# Simple8085.net
KiCad netlist of a schematic drawn in EAGLE
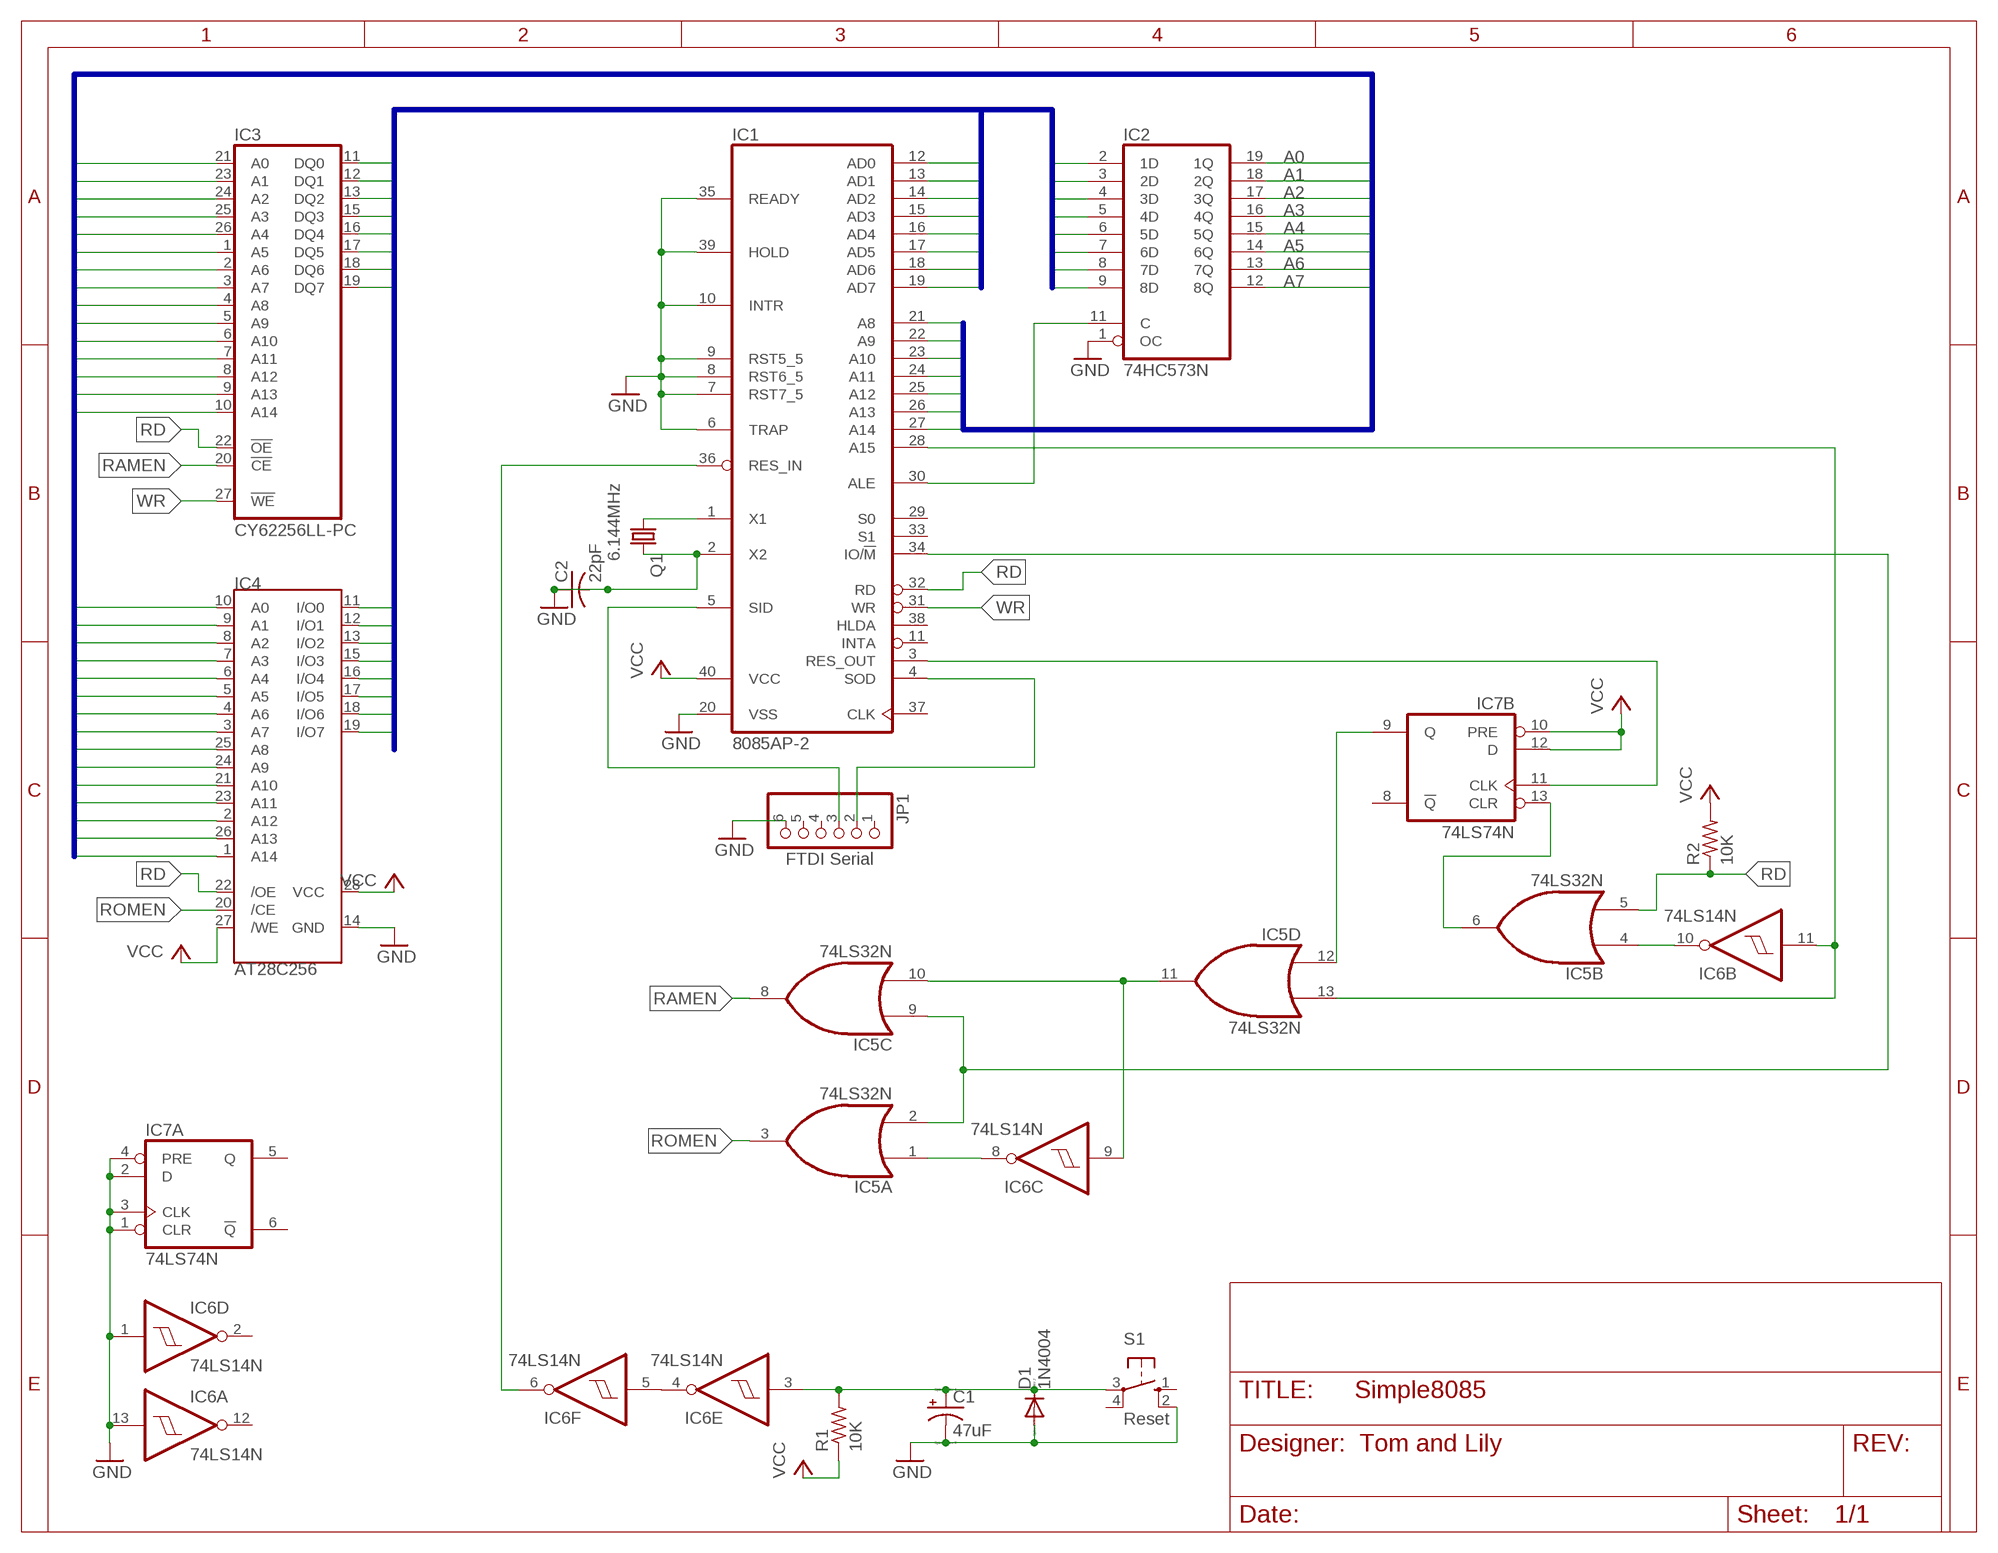
[diagram p0: schematic, sheet 1]

(export (version "E")
  (design (tool "Eeschema 10.0.6"))
  (components
    (comp (ref "C1")
      (value "47uF")
      (footprint "eagle-import:PANASONIC_A")
      (libsource (lib "eagle-import") (part "CPOL-USA"))
    )
    (comp (ref "C2")
      (value "22pF")
      (footprint "eagle-import:C025-050X050")
      (libsource (lib "eagle-import") (part "C-US025-050X050"))
    )
    (comp (ref "D1")
      (value "1N4004")
      (footprint "eagle-import:DO41-10")
      (libsource (lib "eagle-import") (part "1N4004"))
    )
    (comp (ref "IC1")
      (value "8085AP-2")
      (footprint "eagle-import:DIL40")
      (libsource (lib "eagle-import") (part "8085"))
    )
    (comp (ref "IC2")
      (value "74HC573N")
      (footprint "eagle-import:DIL20")
      (libsource (lib "eagle-import") (part "74573NHC"))
    )
    (comp (ref "IC3")
      (value "CY62256LL-PC")
      (footprint "eagle-import:DIL28-6")
      (libsource (lib "eagle-import") (part "CY62256LL-?PC"))
    )
    (comp (ref "IC4")
      (value "AT28C256")
      (footprint "eagle-import:DIL28-6")
      (libsource (lib "eagle-import") (part "AT28C256-28DIP"))
    )
    (comp (ref "IC5")
      (value "74LS32N")
      (footprint "eagle-import:DIL14")
      (libsource (lib "eagle-import") (part "7432NLS"))
    )
    (comp (ref "IC6")
      (value "74LS14N")
      (footprint "eagle-import:DIL14")
      (libsource (lib "eagle-import") (part "7414NLS"))
    )
    (comp (ref "IC7")
      (value "74LS74N")
      (footprint "eagle-import:DIL14")
      (libsource (lib "eagle-import") (part "7474NLS"))
    )
    (comp (ref "JP1")
      (value "FTDI Serial")
      (footprint "eagle-import:1X06")
      (libsource (lib "eagle-import") (part "PINHD-1X6"))
    )
    (comp (ref "Q1")
      (value "6.144MHz")
      (footprint "eagle-import:HC49U-H")
      (libsource (lib "eagle-import") (part "CRYSTALHC49U-H"))
    )
    (comp (ref "R1")
      (value "10K")
      (footprint "eagle-import:0204_5")
      (libsource (lib "eagle-import") (part "R-US_0204/5"))
    )
    (comp (ref "R2")
      (value "10K")
      (footprint "eagle-import:0204_5")
      (libsource (lib "eagle-import") (part "R-US_0204/5"))
    )
    (comp (ref "S1")
      (value "Reset")
      (footprint "eagle-import:B3F-10XX")
      (fields (field (name "MPN") "B3F-1000"))
      (libsource (lib "eagle-import") (part "10-XX"))
    )
  )
  (nets
    (net (code "1") (name "/A0") (class "Default")
      (node (ref "IC2") (pin "19") (pinfunction "1Q_19") (pintype "tri_state"))
      (node (ref "IC3") (pin "21") (pinfunction "A0_21") (pintype "input"))
      (node (ref "IC4") (pin "10") (pinfunction "A0_10") (pintype "input"))
    )
    (net (code "2") (name "/A1") (class "Default")
      (node (ref "IC2") (pin "18") (pinfunction "2Q_18") (pintype "tri_state"))
      (node (ref "IC3") (pin "23") (pinfunction "A1_23") (pintype "input"))
      (node (ref "IC4") (pin "9") (pinfunction "A1_9") (pintype "input"))
    )
    (net (code "3") (name "/A2") (class "Default")
      (node (ref "IC2") (pin "17") (pinfunction "3Q_17") (pintype "tri_state"))
      (node (ref "IC3") (pin "24") (pinfunction "A2_24") (pintype "input"))
      (node (ref "IC4") (pin "8") (pinfunction "A2_8") (pintype "input"))
    )
    (net (code "4") (name "/A3") (class "Default")
      (node (ref "IC2") (pin "16") (pinfunction "4Q_16") (pintype "tri_state"))
      (node (ref "IC3") (pin "25") (pinfunction "A3_25") (pintype "input"))
      (node (ref "IC4") (pin "7") (pinfunction "A3_7") (pintype "input"))
    )
    (net (code "5") (name "/A4") (class "Default")
      (node (ref "IC2") (pin "15") (pinfunction "5Q_15") (pintype "tri_state"))
      (node (ref "IC3") (pin "26") (pinfunction "A4_26") (pintype "input"))
      (node (ref "IC4") (pin "6") (pinfunction "A4_6") (pintype "input"))
    )
    (net (code "6") (name "/A5") (class "Default")
      (node (ref "IC2") (pin "14") (pinfunction "6Q_14") (pintype "tri_state"))
      (node (ref "IC3") (pin "1") (pinfunction "A5_1") (pintype "input"))
      (node (ref "IC4") (pin "5") (pinfunction "A5_5") (pintype "input"))
    )
    (net (code "7") (name "/A6") (class "Default")
      (node (ref "IC2") (pin "13") (pinfunction "7Q_13") (pintype "tri_state"))
      (node (ref "IC3") (pin "2") (pinfunction "A6_2") (pintype "input"))
      (node (ref "IC4") (pin "4") (pinfunction "A6_4") (pintype "input"))
    )
    (net (code "8") (name "/A7") (class "Default")
      (node (ref "IC2") (pin "12") (pinfunction "8Q_12") (pintype "tri_state"))
      (node (ref "IC3") (pin "3") (pinfunction "A7_3") (pintype "input"))
      (node (ref "IC4") (pin "3") (pinfunction "A7_3") (pintype "input"))
    )
    (net (code "9") (name "/A8") (class "Default")
      (node (ref "IC1") (pin "21") (pinfunction "A8_21") (pintype "output"))
      (node (ref "IC3") (pin "4") (pinfunction "A8_4") (pintype "input"))
      (node (ref "IC4") (pin "25") (pinfunction "A8_25") (pintype "input"))
    )
    (net (code "10") (name "/A9") (class "Default")
      (node (ref "IC1") (pin "22") (pinfunction "A9_22") (pintype "output"))
      (node (ref "IC3") (pin "5") (pinfunction "A9_5") (pintype "input"))
      (node (ref "IC4") (pin "24") (pinfunction "A9_24") (pintype "input"))
    )
    (net (code "11") (name "/A10") (class "Default")
      (node (ref "IC1") (pin "23") (pinfunction "A10_23") (pintype "output"))
      (node (ref "IC3") (pin "6") (pinfunction "A10_6") (pintype "input"))
      (node (ref "IC4") (pin "21") (pinfunction "A10_21") (pintype "input"))
    )
    (net (code "12") (name "/A11") (class "Default")
      (node (ref "IC1") (pin "24") (pinfunction "A11_24") (pintype "output"))
      (node (ref "IC3") (pin "7") (pinfunction "A11_7") (pintype "input"))
      (node (ref "IC4") (pin "23") (pinfunction "A11_23") (pintype "input"))
    )
    (net (code "13") (name "/A12") (class "Default")
      (node (ref "IC1") (pin "25") (pinfunction "A12_25") (pintype "output"))
      (node (ref "IC3") (pin "8") (pinfunction "A12_8") (pintype "input"))
      (node (ref "IC4") (pin "2") (pinfunction "A12_2") (pintype "input"))
    )
    (net (code "14") (name "/A13") (class "Default")
      (node (ref "IC1") (pin "26") (pinfunction "A13_26") (pintype "output"))
      (node (ref "IC3") (pin "9") (pinfunction "A13_9") (pintype "input"))
      (node (ref "IC4") (pin "26") (pinfunction "A13_26") (pintype "input"))
    )
    (net (code "15") (name "/A14") (class "Default")
      (node (ref "IC1") (pin "27") (pinfunction "A14_27") (pintype "output"))
      (node (ref "IC3") (pin "10") (pinfunction "A14_10") (pintype "input"))
      (node (ref "IC4") (pin "1") (pinfunction "A14_1") (pintype "input"))
    )
    (net (code "16") (name "/D0") (class "Default")
      (node (ref "IC1") (pin "12") (pinfunction "AD0_12") (pintype "bidirectional"))
      (node (ref "IC2") (pin "2") (pinfunction "1D_2") (pintype "input"))
      (node (ref "IC3") (pin "11") (pinfunction "DQ0_11") (pintype "bidirectional"))
      (node (ref "IC4") (pin "11") (pinfunction "I/O0_11") (pintype "bidirectional"))
    )
    (net (code "17") (name "/D1") (class "Default")
      (node (ref "IC1") (pin "13") (pinfunction "AD1_13") (pintype "bidirectional"))
      (node (ref "IC2") (pin "3") (pinfunction "2D_3") (pintype "input"))
      (node (ref "IC3") (pin "12") (pinfunction "DQ1_12") (pintype "bidirectional"))
      (node (ref "IC4") (pin "12") (pinfunction "I/O1_12") (pintype "bidirectional"))
    )
    (net (code "18") (name "/D2") (class "Default")
      (node (ref "IC1") (pin "14") (pinfunction "AD2_14") (pintype "bidirectional"))
      (node (ref "IC2") (pin "4") (pinfunction "3D_4") (pintype "input"))
      (node (ref "IC3") (pin "13") (pinfunction "DQ2_13") (pintype "bidirectional"))
      (node (ref "IC4") (pin "13") (pinfunction "I/O2_13") (pintype "bidirectional"))
    )
    (net (code "19") (name "/D3") (class "Default")
      (node (ref "IC1") (pin "15") (pinfunction "AD3_15") (pintype "bidirectional"))
      (node (ref "IC2") (pin "5") (pinfunction "4D_5") (pintype "input"))
      (node (ref "IC3") (pin "15") (pinfunction "DQ3_15") (pintype "bidirectional"))
      (node (ref "IC4") (pin "15") (pinfunction "I/O3_15") (pintype "bidirectional"))
    )
    (net (code "20") (name "/D4") (class "Default")
      (node (ref "IC1") (pin "16") (pinfunction "AD4_16") (pintype "bidirectional"))
      (node (ref "IC2") (pin "6") (pinfunction "5D_6") (pintype "input"))
      (node (ref "IC3") (pin "16") (pinfunction "DQ4_16") (pintype "bidirectional"))
      (node (ref "IC4") (pin "16") (pinfunction "I/O4_16") (pintype "bidirectional"))
    )
    (net (code "21") (name "/D5") (class "Default")
      (node (ref "IC1") (pin "17") (pinfunction "AD5_17") (pintype "bidirectional"))
      (node (ref "IC2") (pin "7") (pinfunction "6D_7") (pintype "input"))
      (node (ref "IC3") (pin "17") (pinfunction "DQ5_17") (pintype "bidirectional"))
      (node (ref "IC4") (pin "17") (pinfunction "I/O5_17") (pintype "bidirectional"))
    )
    (net (code "22") (name "/D6") (class "Default")
      (node (ref "IC1") (pin "18") (pinfunction "AD6_18") (pintype "bidirectional"))
      (node (ref "IC2") (pin "8") (pinfunction "7D_8") (pintype "input"))
      (node (ref "IC3") (pin "18") (pinfunction "DQ6_18") (pintype "bidirectional"))
      (node (ref "IC4") (pin "18") (pinfunction "I/O6_18") (pintype "bidirectional"))
    )
    (net (code "23") (name "/D7") (class "Default")
      (node (ref "IC1") (pin "19") (pinfunction "AD7_19") (pintype "bidirectional"))
      (node (ref "IC2") (pin "9") (pinfunction "8D_9") (pintype "input"))
      (node (ref "IC3") (pin "19") (pinfunction "DQ7_19") (pintype "bidirectional"))
      (node (ref "IC4") (pin "19") (pinfunction "I/O7_19") (pintype "bidirectional"))
    )
    (net (code "24") (name "GND") (class "Default")
      (node (ref "C1") (pin "-") (pinfunction "-_-") (pintype "passive"))
      (node (ref "C2") (pin "1") (pinfunction "1_1") (pintype "passive"))
      (node (ref "C2") (pin "2") (pinfunction "2_2") (pintype "passive"))
      (node (ref "D1") (pin "A") (pinfunction "A_A") (pintype "passive"))
      (node (ref "IC1") (pin "10") (pinfunction "INTR_10") (pintype "input"))
      (node (ref "IC1") (pin "2") (pinfunction "X2_2") (pintype "input"))
      (node (ref "IC1") (pin "20") (pinfunction "VSS_20") (pintype "power_in"))
      (node (ref "IC1") (pin "35") (pinfunction "READY_35") (pintype "input"))
      (node (ref "IC1") (pin "39") (pinfunction "HOLD_39") (pintype "input"))
      (node (ref "IC1") (pin "6") (pinfunction "TRAP_6") (pintype "input"))
      (node (ref "IC1") (pin "7") (pinfunction "RST7_5_7") (pintype "input"))
      (node (ref "IC1") (pin "8") (pinfunction "RST6_5_8") (pintype "input"))
      (node (ref "IC1") (pin "9") (pinfunction "RST5_5_9") (pintype "input"))
      (node (ref "IC2") (pin "1") (pinfunction "OC_1") (pintype "input"))
      (node (ref "IC4") (pin "14") (pinfunction "GND_14") (pintype "power_in"))
      (node (ref "IC6") (pin "1") (pinfunction "I_1") (pintype "input"))
      (node (ref "IC6") (pin "13") (pinfunction "I_13") (pintype "input"))
      (node (ref "IC7") (pin "1") (pinfunction "CLR_1") (pintype "input"))
      (node (ref "IC7") (pin "2") (pinfunction "D_2") (pintype "input"))
      (node (ref "IC7") (pin "3") (pinfunction "CLK_3") (pintype "input"))
      (node (ref "IC7") (pin "4") (pinfunction "PRE_4") (pintype "input"))
      (node (ref "JP1") (pin "6") (pinfunction "6_6") (pintype "passive"))
      (node (ref "Q1") (pin "2") (pinfunction "2_2") (pintype "passive"))
      (node (ref "S1") (pin "2") (pinfunction "S1_2") (pintype "passive"))
    )
    (net (code "25") (name "Net-(IC1-A15)") (class "Default")
      (node (ref "IC1") (pin "28") (pinfunction "A15_28") (pintype "output"))
      (node (ref "IC5") (pin "13") (pinfunction "I1_13") (pintype "input"))
      (node (ref "IC6") (pin "11") (pinfunction "I_11") (pintype "input"))
    )
    (net (code "26") (name "Net-(IC1-ALE)") (class "Default")
      (node (ref "IC1") (pin "30") (pinfunction "ALE_30") (pintype "output"))
      (node (ref "IC2") (pin "11") (pinfunction "C_11") (pintype "input"))
    )
    (net (code "27") (name "Net-(IC1-IO{slash}~{M})") (class "Default")
      (node (ref "IC1") (pin "34") (pinfunction "IO/~{M}_34") (pintype "output"))
      (node (ref "IC5") (pin "2") (pinfunction "I1_2") (pintype "input"))
      (node (ref "IC5") (pin "9") (pinfunction "I0_9") (pintype "input"))
    )
    (net (code "28") (name "Net-(IC1-RES_IN)") (class "Default")
      (node (ref "IC1") (pin "36") (pinfunction "RES_IN_36") (pintype "input"))
      (node (ref "IC6") (pin "6") (pinfunction "O_6") (pintype "output"))
    )
    (net (code "29") (name "Net-(IC1-RES_OUT)") (class "Default")
      (node (ref "IC1") (pin "3") (pinfunction "RES_OUT_3") (pintype "output"))
      (node (ref "IC7") (pin "11") (pinfunction "CLK_11") (pintype "input"))
    )
    (net (code "30") (name "Net-(IC1-SID)") (class "Default")
      (node (ref "IC1") (pin "5") (pinfunction "SID_5") (pintype "input"))
      (node (ref "JP1") (pin "3") (pinfunction "3_3") (pintype "passive"))
    )
    (net (code "31") (name "Net-(IC1-SOD)") (class "Default")
      (node (ref "IC1") (pin "4") (pinfunction "SOD_4") (pintype "output"))
      (node (ref "JP1") (pin "2") (pinfunction "2_2") (pintype "passive"))
    )
    (net (code "32") (name "Net-(IC1-X1)") (class "Default")
      (node (ref "IC1") (pin "1") (pinfunction "X1_1") (pintype "input"))
      (node (ref "Q1") (pin "1") (pinfunction "1_1") (pintype "passive"))
    )
    (net (code "33") (name "Net-(IC5A-I0)") (class "Default")
      (node (ref "IC5") (pin "1") (pinfunction "I0_1") (pintype "input"))
      (node (ref "IC6") (pin "8") (pinfunction "O_8") (pintype "output"))
    )
    (net (code "34") (name "Net-(IC5B-I0)") (class "Default")
      (node (ref "IC5") (pin "4") (pinfunction "I0_4") (pintype "input"))
      (node (ref "IC6") (pin "10") (pinfunction "O_10") (pintype "output"))
    )
    (net (code "35") (name "Net-(IC5B-O)") (class "Default")
      (node (ref "IC5") (pin "6") (pinfunction "O_6") (pintype "output"))
      (node (ref "IC7") (pin "13") (pinfunction "CLR_13") (pintype "input"))
    )
    (net (code "36") (name "Net-(IC5C-I1)") (class "Default")
      (node (ref "IC5") (pin "10") (pinfunction "I1_10") (pintype "input"))
      (node (ref "IC5") (pin "11") (pinfunction "O_11") (pintype "output"))
      (node (ref "IC6") (pin "9") (pinfunction "I_9") (pintype "input"))
    )
    (net (code "37") (name "Net-(IC5D-I0)") (class "Default")
      (node (ref "IC5") (pin "12") (pinfunction "I0_12") (pintype "input"))
      (node (ref "IC7") (pin "9") (pinfunction "Q_9") (pintype "output"))
    )
    (net (code "38") (name "Net-(IC6E-I)") (class "Default")
      (node (ref "C1") (pin "+") (pinfunction "+_+") (pintype "passive"))
      (node (ref "D1") (pin "C") (pinfunction "C_C") (pintype "passive"))
      (node (ref "IC6") (pin "3") (pinfunction "I_3") (pintype "input"))
      (node (ref "R1") (pin "2") (pinfunction "2_2") (pintype "passive"))
      (node (ref "S1") (pin "3") (pinfunction "P_3") (pintype "passive"))
    )
    (net (code "39") (name "Net-(IC6E-O)") (class "Default")
      (node (ref "IC6") (pin "4") (pinfunction "O_4") (pintype "output"))
      (node (ref "IC6") (pin "5") (pinfunction "I_5") (pintype "input"))
    )
    (net (code "40") (name "RAMEN") (class "Default")
      (node (ref "IC3") (pin "20") (pinfunction "~{CE}_20") (pintype "input"))
      (node (ref "IC5") (pin "8") (pinfunction "O_8") (pintype "output"))
    )
    (net (code "41") (name "RD") (class "Default")
      (node (ref "IC1") (pin "32") (pinfunction "RD_32") (pintype "output"))
      (node (ref "IC3") (pin "22") (pinfunction "~{OE}_22") (pintype "input"))
      (node (ref "IC4") (pin "22") (pinfunction "/OE_22") (pintype "input"))
      (node (ref "IC5") (pin "5") (pinfunction "I1_5") (pintype "input"))
      (node (ref "R2") (pin "1") (pinfunction "1_1") (pintype "passive"))
    )
    (net (code "42") (name "ROMEN") (class "Default")
      (node (ref "IC4") (pin "20") (pinfunction "/CE_20") (pintype "input"))
      (node (ref "IC5") (pin "3") (pinfunction "O_3") (pintype "output"))
    )
    (net (code "43") (name "VCC") (class "Default")
      (node (ref "IC1") (pin "40") (pinfunction "VCC_40") (pintype "power_in"))
      (node (ref "IC4") (pin "27") (pinfunction "/WE_27") (pintype "input"))
      (node (ref "IC4") (pin "28") (pinfunction "VCC_28") (pintype "power_in"))
      (node (ref "IC7") (pin "10") (pinfunction "PRE_10") (pintype "input"))
      (node (ref "IC7") (pin "12") (pinfunction "D_12") (pintype "input"))
      (node (ref "R1") (pin "1") (pinfunction "1_1") (pintype "passive"))
      (node (ref "R2") (pin "2") (pinfunction "2_2") (pintype "passive"))
    )
    (net (code "44") (name "WR") (class "Default")
      (node (ref "IC1") (pin "31") (pinfunction "WR_31") (pintype "output"))
      (node (ref "IC3") (pin "27") (pinfunction "~{WE}_27") (pintype "input"))
    )
    (net (code "45") (name "unconnected-(IC1-CLK-Pad37)") (class "Default")
      (node (ref "IC1") (pin "37") (pinfunction "CLK_37") (pintype "output"))
    )
    (net (code "46") (name "unconnected-(IC1-HLDA-Pad38)") (class "Default")
      (node (ref "IC1") (pin "38") (pinfunction "HLDA_38") (pintype "output"))
    )
    (net (code "47") (name "unconnected-(IC1-INTA-Pad11)") (class "Default")
      (node (ref "IC1") (pin "11") (pinfunction "INTA_11") (pintype "output"))
    )
    (net (code "48") (name "unconnected-(IC1-S0-Pad29)") (class "Default")
      (node (ref "IC1") (pin "29") (pinfunction "S0_29") (pintype "output"))
    )
    (net (code "49") (name "unconnected-(IC1-S1-Pad33)") (class "Default")
      (node (ref "IC1") (pin "33") (pinfunction "S1_33") (pintype "output"))
    )
    (net (code "50") (name "unconnected-(IC6A-O-Pad12)") (class "Default")
      (node (ref "IC6") (pin "12") (pinfunction "O_12") (pintype "output"))
    )
    (net (code "51") (name "unconnected-(IC6D-O-Pad2)") (class "Default")
      (node (ref "IC6") (pin "2") (pinfunction "O_2") (pintype "output"))
    )
    (net (code "52") (name "unconnected-(IC7A-Q-Pad5)") (class "Default")
      (node (ref "IC7") (pin "5") (pinfunction "Q_5") (pintype "output"))
    )
    (net (code "53") (name "unconnected-(IC7A-~{Q}-Pad6)") (class "Default")
      (node (ref "IC7") (pin "6") (pinfunction "~{Q}_6") (pintype "output"))
    )
    (net (code "54") (name "unconnected-(IC7B-~{Q}-Pad8)") (class "Default")
      (node (ref "IC7") (pin "8") (pinfunction "~{Q}_8") (pintype "output"))
    )
    (net (code "55") (name "unconnected-(JP1-Pad1)") (class "Default")
      (node (ref "JP1") (pin "1") (pinfunction "1_1") (pintype "passive"))
    )
    (net (code "56") (name "unconnected-(JP1-Pad4)") (class "Default")
      (node (ref "JP1") (pin "4") (pinfunction "4_4") (pintype "passive"))
    )
    (net (code "57") (name "unconnected-(JP1-Pad5)") (class "Default")
      (node (ref "JP1") (pin "5") (pinfunction "5_5") (pintype "passive"))
    )
    (net (code "58") (name "unconnected-(S1-P1-Pad4)") (class "Default")
      (node (ref "S1") (pin "4") (pinfunction "P1_4") (pintype "passive"))
    )
    (net (code "59") (name "unconnected-(S1-S-Pad1)") (class "Default")
      (node (ref "S1") (pin "1") (pinfunction "S_1") (pintype "passive"))
    )
  )
)
